# Sensor_Board.net
KiCad netlist of a schematic drawn in Altium Designer
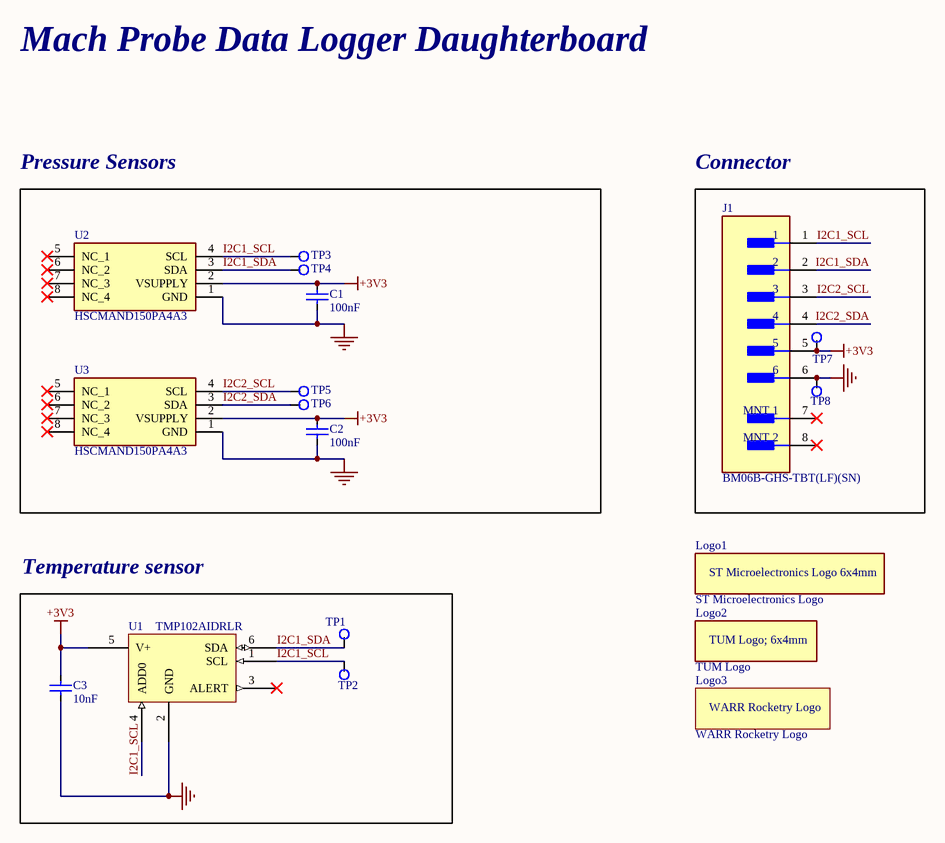
[diagram p0: Sensor_Board.SchDoc]

(export (version "E")
  (design (tool "Eeschema 10.0.6"))
  (components
    (comp (ref "C1")
      (value "100nF")
      (footprint "CAP_0603")
      (fields (field (name "Comment") "C_0603_100n_5%_50V"))
      (libsource (lib "WARR Rocketry Electronics") (part "Capacitor"))
    )
    (comp (ref "C2")
      (value "100nF")
      (footprint "CAP_0603")
      (fields (field (name "Comment") "C_0603_100n_5%_50V"))
      (libsource (lib "WARR Rocketry Electronics") (part "Capacitor"))
    )
    (comp (ref "C3")
      (value "10nF")
      (footprint "CAP_0603")
      (fields (field (name "TOLERANCE") "5%") (field (name "Comment") "C_0603_10n_5%_50V"))
      (libsource (lib "WARR Rocketry Electronics") (part "Capacitor"))
    )
    (comp (ref "J1")
      (value "BM06B-GHS-TBT(LF)(SN)")
      (footprint "FP-BM06B-GHS-TBT_LF_SN-MFG")
      (description "CONN HEADER SMD 6POS 1.25MM")
      (libsource (lib "Altium Content Vault") (part "ed24c53d9ba001d1a2a686240a95171"))
    )
    (comp (ref "Logo1")
      (value "ST Microelectronics Logo")
      (footprint "New footprint 1")
      (description "ST Microelectronics Logo 6x4mm")
      (libsource (lib "WARR Rocketry Electronics") (part "ST Microelectronics Logo"))
    )
    (comp (ref "Logo2")
      (value "TUM Logo")
      (footprint "New footprint 1")
      (description "6 x 4 mm TUM Logo")
      (libsource (lib "WARR Rocketry Electronics") (part "TUM Logo"))
    )
    (comp (ref "Logo3")
      (value "WARR Rocketry Logo")
      (footprint "WARR Rocketry Logo-Footprint-1")
      (description "Warr Rocketry Logo")
      (libsource (lib "WARR Rocketry Electronics") (part "WARR Rocketry Logo-Symbol-1"))
    )
    (comp (ref "TP1")
      (value "Testpoint")
      (footprint "Testpoint-Footprint-1")
      (description "Schematic for Testpoint")
      (libsource (lib "WARR Rocketry Electronics") (part "TP?"))
    )
    (comp (ref "TP2")
      (value "Testpoint")
      (footprint "Testpoint-Footprint-1")
      (description "Schematic for Testpoint")
      (libsource (lib "WARR Rocketry Electronics") (part "TP?"))
    )
    (comp (ref "TP3")
      (value "Testpoint")
      (footprint "Testpoint-Footprint-1")
      (description "Schematic for Testpoint")
      (libsource (lib "WARR Rocketry Electronics") (part "TP?"))
    )
    (comp (ref "TP4")
      (value "Testpoint")
      (footprint "Testpoint-Footprint-1")
      (description "Schematic for Testpoint")
      (libsource (lib "WARR Rocketry Electronics") (part "TP?"))
    )
    (comp (ref "TP5")
      (value "Testpoint")
      (footprint "Testpoint-Footprint-1")
      (description "Schematic for Testpoint")
      (libsource (lib "WARR Rocketry Electronics") (part "TP?"))
    )
    (comp (ref "TP6")
      (value "Testpoint")
      (footprint "Testpoint-Footprint-1")
      (description "Schematic for Testpoint")
      (libsource (lib "WARR Rocketry Electronics") (part "TP?"))
    )
    (comp (ref "TP7")
      (value "Testpoint")
      (footprint "Testpoint-Footprint-1")
      (description "Schematic for Testpoint")
      (libsource (lib "WARR Rocketry Electronics") (part "TP?"))
    )
    (comp (ref "TP8")
      (value "Testpoint")
      (footprint "Testpoint-Footprint-1")
      (description "Schematic for Testpoint")
      (libsource (lib "WARR Rocketry Electronics") (part "TP?"))
    )
    (comp (ref "U1")
      (value "TMP102AIDRLR")
      (footprint "SOTFL127P600-8N")
      (description "Digital Temperature Sensor, I2C,12 Bit(s), ±2C, SOT563")
      (fields
        (field (name "LCSC PART NUMBER") "C99269")
        (field (name "MOUSER PART NUMBER") "595-TMP102AIDRLR")
      )
      (libsource (lib "WARR Rocketry") (part "TMP102AIDRLR-Symbol-1"))
    )
    (comp (ref "U2")
      (value "HSCMAND150PA4A3")
      (footprint "SamacSys:HSCMAND150PA4A3")
      (description "Undefined or Miscellaneous")
      (fields (field (name "MOUSER PART NUMBER") "785-HSCMAND150PA4A3"))
      (libsource (lib "SamacSys") (part "HSCMAND150PA4A3"))
    )
    (comp (ref "U3")
      (value "HSCMAND150PA4A3")
      (footprint "SamacSys:HSCMAND150PA4A3")
      (description "Undefined or Miscellaneous")
      (fields (field (name "MOUSER PART NUMBER") "785-HSCMAND150PA4A3"))
      (libsource (lib "SamacSys") (part "HSCMAND150PA4A3"))
    )
  )
  (nets
    (net (code "1") (name "+3V3") (class "Default")
      (node (ref "C1") (pin "1") (pinfunction "1_1") (pintype "passive"))
      (node (ref "C2") (pin "1") (pinfunction "1_1") (pintype "passive"))
      (node (ref "C3") (pin "1") (pinfunction "1_1") (pintype "passive"))
      (node (ref "J1") (pin "5") (pinfunction "5_5") (pintype "passive"))
      (node (ref "TP7") (pin "1") (pinfunction "1_1") (pintype "passive"))
      (node (ref "U1") (pin "5") (pinfunction "V+_5") (pintype "power_in"))
      (node (ref "U2") (pin "2") (pinfunction "VSUPPLY_2") (pintype "passive"))
      (node (ref "U3") (pin "2") (pinfunction "VSUPPLY_2") (pintype "passive"))
    )
    (net (code "2") (name "/I2C1_SCL") (class "Default")
      (node (ref "J1") (pin "1") (pinfunction "1_1") (pintype "passive"))
      (node (ref "TP2") (pin "1") (pinfunction "1_1") (pintype "passive"))
      (node (ref "TP3") (pin "1") (pinfunction "1_1") (pintype "passive"))
      (node (ref "U1") (pin "1") (pinfunction "SCL_1") (pintype "input"))
      (node (ref "U1") (pin "4") (pinfunction "ADD0_4") (pintype "input"))
      (node (ref "U2") (pin "4") (pinfunction "SCL_4") (pintype "passive"))
    )
    (net (code "3") (name "/I2C1_SDA") (class "Default")
      (node (ref "J1") (pin "2") (pinfunction "2_2") (pintype "passive"))
      (node (ref "TP1") (pin "1") (pinfunction "1_1") (pintype "passive"))
      (node (ref "TP4") (pin "1") (pinfunction "1_1") (pintype "passive"))
      (node (ref "U1") (pin "6") (pinfunction "SDA_6") (pintype "bidirectional"))
      (node (ref "U2") (pin "3") (pinfunction "SDA_3") (pintype "passive"))
    )
    (net (code "4") (name "/I2C2_SCL") (class "Default")
      (node (ref "J1") (pin "3") (pinfunction "3_3") (pintype "passive"))
      (node (ref "TP5") (pin "1") (pinfunction "1_1") (pintype "passive"))
      (node (ref "U3") (pin "4") (pinfunction "SCL_4") (pintype "passive"))
    )
    (net (code "5") (name "/I2C2_SDA") (class "Default")
      (node (ref "J1") (pin "4") (pinfunction "4_4") (pintype "passive"))
      (node (ref "TP6") (pin "1") (pinfunction "1_1") (pintype "passive"))
      (node (ref "U3") (pin "3") (pinfunction "SDA_3") (pintype "passive"))
    )
    (net (code "6") (name "GND") (class "Default")
      (node (ref "C1") (pin "2") (pinfunction "2_2") (pintype "passive"))
      (node (ref "C2") (pin "2") (pinfunction "2_2") (pintype "passive"))
      (node (ref "C3") (pin "2") (pinfunction "2_2") (pintype "passive"))
      (node (ref "J1") (pin "6") (pinfunction "6_6") (pintype "passive"))
      (node (ref "TP8") (pin "1") (pinfunction "1_1") (pintype "passive"))
      (node (ref "U1") (pin "2") (pinfunction "GND_2") (pintype "power_in"))
      (node (ref "U2") (pin "1") (pinfunction "GND_1") (pintype "passive"))
      (node (ref "U3") (pin "1") (pinfunction "GND_1") (pintype "passive"))
    )
    (net (code "7") (name "unconnected-(J1-MNT_1-Pad7)") (class "Default")
      (node (ref "J1") (pin "7") (pinfunction "MNT_1_7") (pintype "passive+no_connect"))
    )
    (net (code "8") (name "unconnected-(J1-MNT_2-Pad8)") (class "Default")
      (node (ref "J1") (pin "8") (pinfunction "MNT_2_8") (pintype "passive+no_connect"))
    )
    (net (code "9") (name "unconnected-(U1-ALERT-Pad3)") (class "Default")
      (node (ref "U1") (pin "3") (pinfunction "ALERT_3") (pintype "output+no_connect"))
    )
    (net (code "10") (name "unconnected-(U2-NC_1-Pad5)") (class "Default")
      (node (ref "U2") (pin "5") (pinfunction "NC_1_5") (pintype "passive+no_connect"))
    )
    (net (code "11") (name "unconnected-(U2-NC_2-Pad6)") (class "Default")
      (node (ref "U2") (pin "6") (pinfunction "NC_2_6") (pintype "passive+no_connect"))
    )
    (net (code "12") (name "unconnected-(U2-NC_3-Pad7)") (class "Default")
      (node (ref "U2") (pin "7") (pinfunction "NC_3_7") (pintype "passive+no_connect"))
    )
    (net (code "13") (name "unconnected-(U2-NC_4-Pad8)") (class "Default")
      (node (ref "U2") (pin "8") (pinfunction "NC_4_8") (pintype "passive+no_connect"))
    )
    (net (code "14") (name "unconnected-(U3-NC_1-Pad5)") (class "Default")
      (node (ref "U3") (pin "5") (pinfunction "NC_1_5") (pintype "passive+no_connect"))
    )
    (net (code "15") (name "unconnected-(U3-NC_2-Pad6)") (class "Default")
      (node (ref "U3") (pin "6") (pinfunction "NC_2_6") (pintype "passive+no_connect"))
    )
    (net (code "16") (name "unconnected-(U3-NC_3-Pad7)") (class "Default")
      (node (ref "U3") (pin "7") (pinfunction "NC_3_7") (pintype "passive+no_connect"))
    )
    (net (code "17") (name "unconnected-(U3-NC_4-Pad8)") (class "Default")
      (node (ref "U3") (pin "8") (pinfunction "NC_4_8") (pintype "passive+no_connect"))
    )
  )
)
